# Bank.net
KiCad netlist of a schematic drawn in Altium Designer
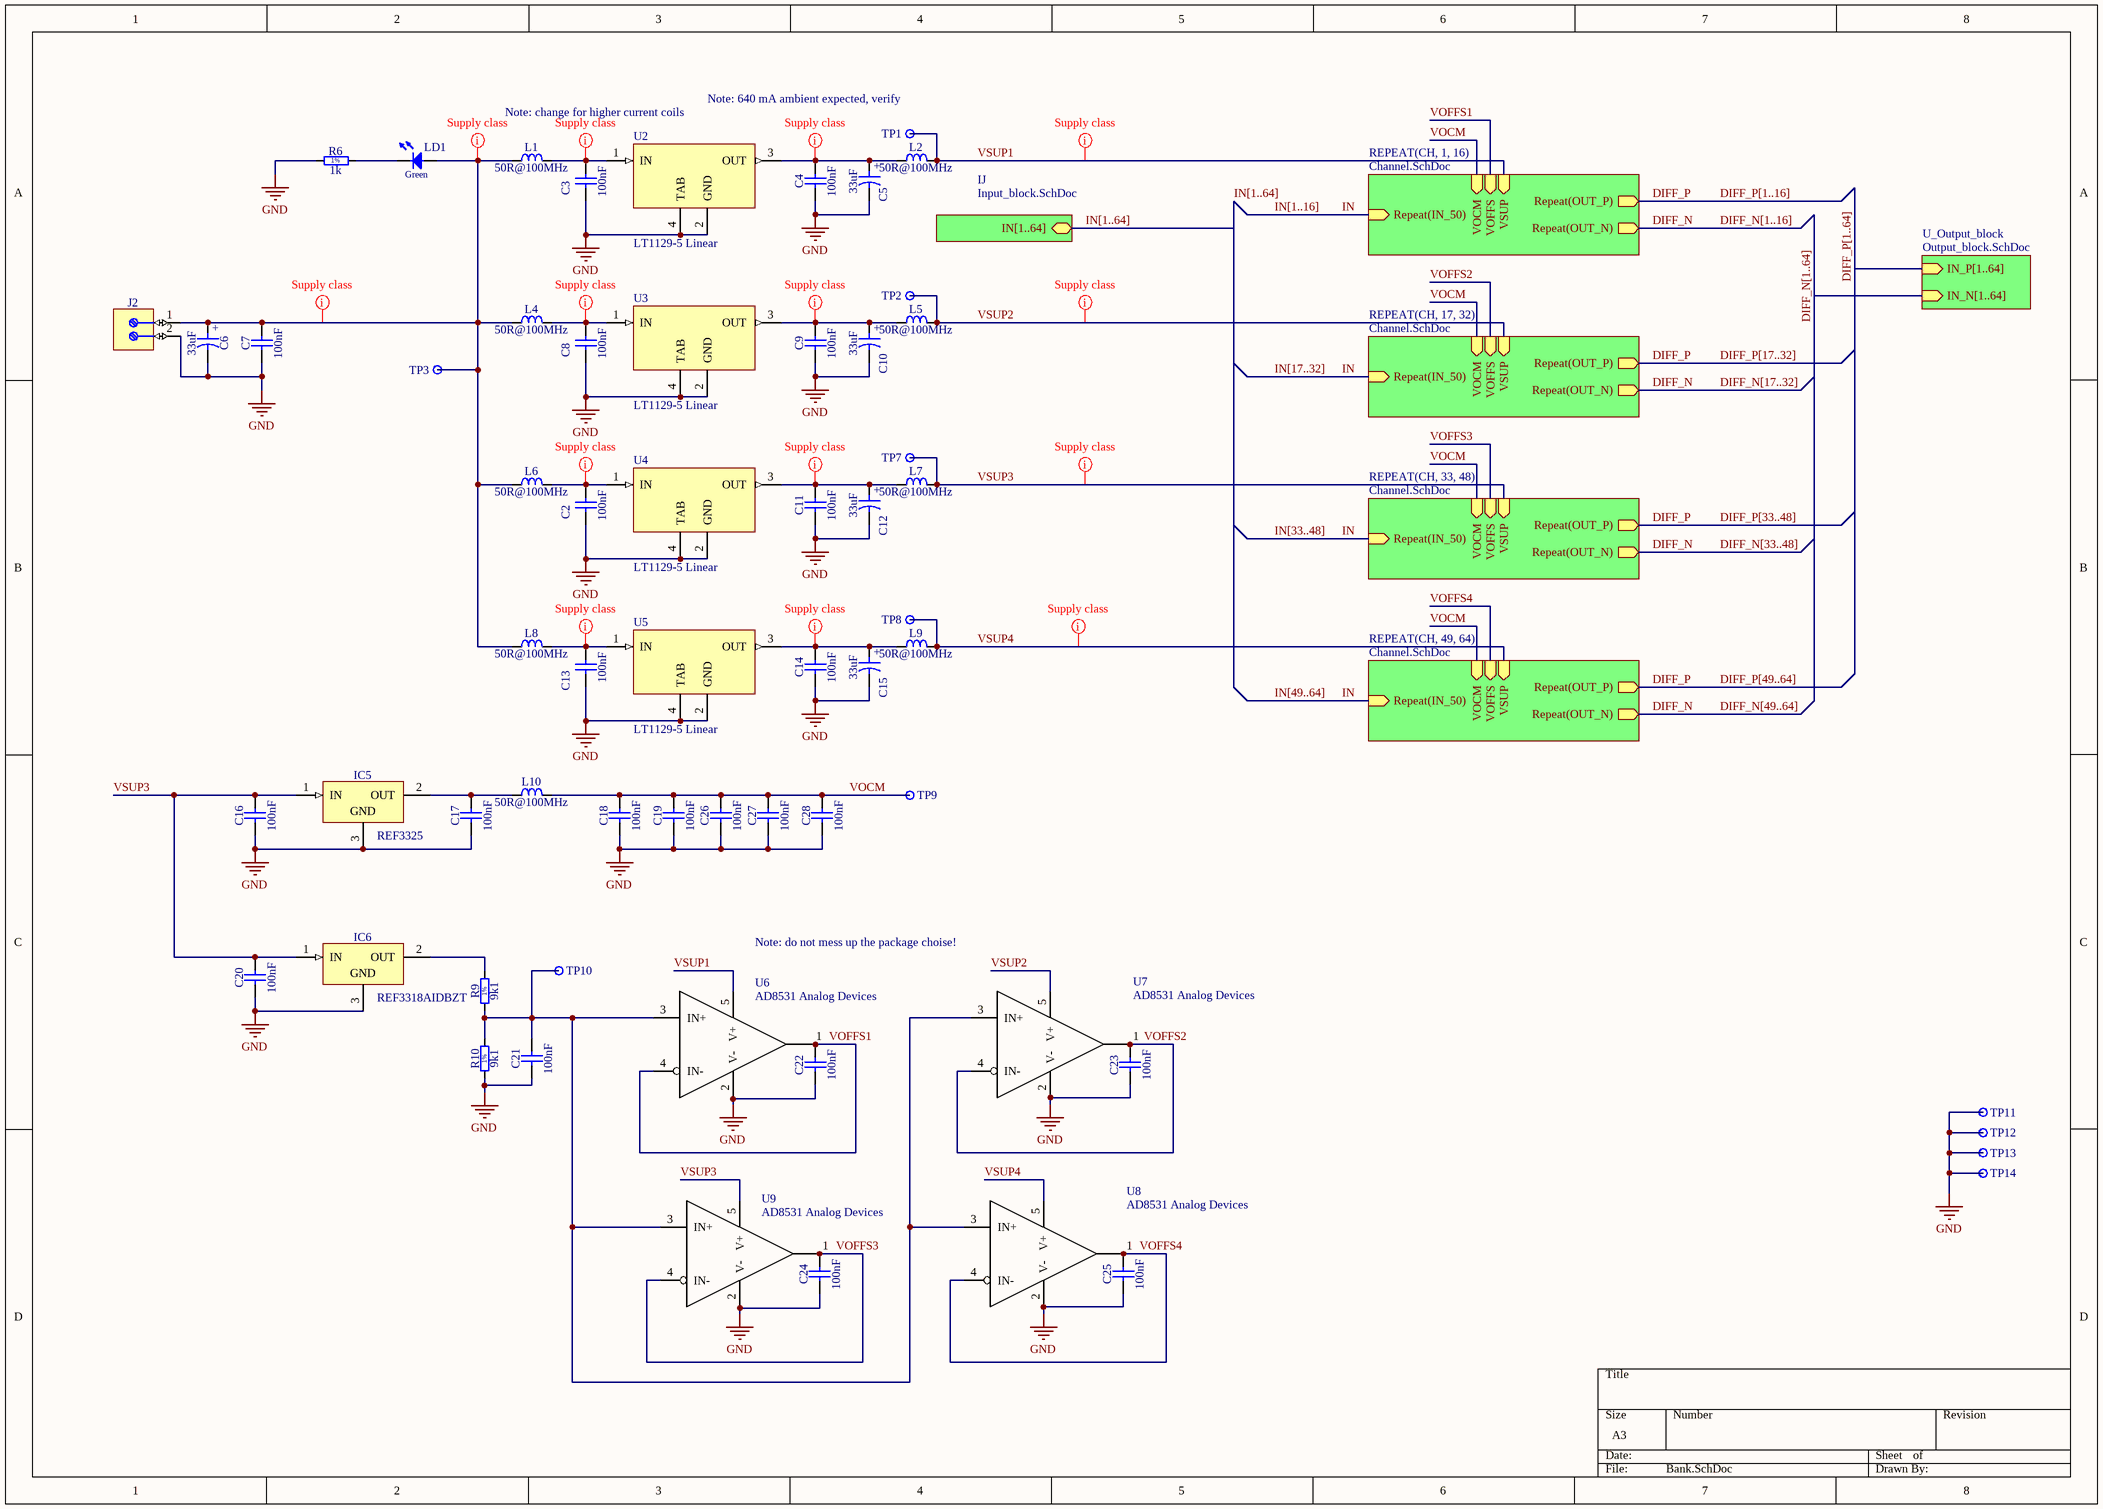
[diagram p0: Bank.SchDoc]

(export (version "E")
  (design (tool "Eeschema 10.0.6"))
  (components
    (comp (ref "C2")
      (value "100nF")
      (footprint "CAPC2012X135N")
      (description "Non-polarised capacitor")
      (fields
        (field (name "PART NUMBER") "CC0805_100NF_50V_10%_X7R")
        (field (name "VOLTAGE") "50V")
        (field (name "AUTHOR") "CERN DEM JLC")
      )
      (libsource (lib "Capacitors") (part "Capacitor - non polarized"))
    )
    (comp (ref "C3")
      (value "100nF")
      (footprint "CAPC2012X135N")
      (description "Non-polarised capacitor")
      (fields
        (field (name "PART NUMBER") "CC0805_100NF_50V_10%_X7R")
        (field (name "VOLTAGE") "50V")
        (field (name "AUTHOR") "CERN DEM JLC")
      )
      (libsource (lib "Capacitors") (part "Capacitor - non polarized"))
    )
    (comp (ref "C4")
      (value "100nF")
      (footprint "CAPC2012X135N")
      (description "Non-polarised capacitor")
      (fields
        (field (name "PART NUMBER") "CC0805_100NF_50V_10%_X7R")
        (field (name "VOLTAGE") "50V")
        (field (name "AUTHOR") "CERN DEM JLC")
      )
      (libsource (lib "Capacitors") (part "Capacitor - non polarized"))
    )
    (comp (ref "C5")
      (value "33uF")
      (footprint "CAPAE660X540N")
      (description "Polarised capacitor")
      (fields
        (field (name "PART NUMBER") "CAE660-540_33UF_25V_20%")
        (field (name "VOLTAGE") "25V")
        (field (name "AUTHOR") "CERN DEM JLC")
      )
      (libsource (lib "Capacitors") (part "Capacitor - polarized"))
    )
    (comp (ref "C6")
      (value "33uF")
      (footprint "CAPAE660X540N")
      (description "Polarised capacitor")
      (fields
        (field (name "PART NUMBER") "CAE660-540_33UF_25V_20%")
        (field (name "VOLTAGE") "25V")
        (field (name "AUTHOR") "CERN DEM JLC")
      )
      (libsource (lib "Capacitors") (part "Capacitor - polarized"))
    )
    (comp (ref "C7")
      (value "100nF")
      (footprint "CAPC2012X135N")
      (description "Non-polarised capacitor")
      (fields
        (field (name "PART NUMBER") "CC0805_100NF_50V_10%_X7R")
        (field (name "VOLTAGE") "50V")
        (field (name "AUTHOR") "CERN DEM JLC")
      )
      (libsource (lib "Capacitors") (part "Capacitor - non polarized"))
    )
    (comp (ref "C8")
      (value "100nF")
      (footprint "CAPC2012X135N")
      (description "Non-polarised capacitor")
      (fields
        (field (name "PART NUMBER") "CC0805_100NF_50V_10%_X7R")
        (field (name "VOLTAGE") "50V")
        (field (name "AUTHOR") "CERN DEM JLC")
      )
      (libsource (lib "Capacitors") (part "Capacitor - non polarized"))
    )
    (comp (ref "C9")
      (value "100nF")
      (footprint "CAPC2012X135N")
      (description "Non-polarised capacitor")
      (fields
        (field (name "PART NUMBER") "CC0805_100NF_50V_10%_X7R")
        (field (name "VOLTAGE") "50V")
        (field (name "AUTHOR") "CERN DEM JLC")
      )
      (libsource (lib "Capacitors") (part "Capacitor - non polarized"))
    )
    (comp (ref "C10")
      (value "33uF")
      (footprint "CAPAE660X540N")
      (description "Polarised capacitor")
      (fields
        (field (name "PART NUMBER") "CAE660-540_33UF_25V_20%")
        (field (name "VOLTAGE") "25V")
        (field (name "AUTHOR") "CERN DEM JLC")
      )
      (libsource (lib "Capacitors") (part "Capacitor - polarized"))
    )
    (comp (ref "C11")
      (value "100nF")
      (footprint "CAPC2012X135N")
      (description "Non-polarised capacitor")
      (fields
        (field (name "PART NUMBER") "CC0805_100NF_50V_10%_X7R")
        (field (name "VOLTAGE") "50V")
        (field (name "AUTHOR") "CERN DEM JLC")
      )
      (libsource (lib "Capacitors") (part "Capacitor - non polarized"))
    )
    (comp (ref "C12")
      (value "33uF")
      (footprint "CAPAE660X540N")
      (description "Polarised capacitor")
      (fields
        (field (name "PART NUMBER") "CAE660-540_33UF_25V_20%")
        (field (name "VOLTAGE") "25V")
        (field (name "AUTHOR") "CERN DEM JLC")
      )
      (libsource (lib "Capacitors") (part "Capacitor - polarized"))
    )
    (comp (ref "C13")
      (value "100nF")
      (footprint "CAPC2012X135N")
      (description "Non-polarised capacitor")
      (fields
        (field (name "PART NUMBER") "CC0805_100NF_50V_10%_X7R")
        (field (name "VOLTAGE") "50V")
        (field (name "AUTHOR") "CERN DEM JLC")
      )
      (libsource (lib "Capacitors") (part "Capacitor - non polarized"))
    )
    (comp (ref "C14")
      (value "100nF")
      (footprint "CAPC2012X135N")
      (description "Non-polarised capacitor")
      (fields
        (field (name "PART NUMBER") "CC0805_100NF_50V_10%_X7R")
        (field (name "VOLTAGE") "50V")
        (field (name "AUTHOR") "CERN DEM JLC")
      )
      (libsource (lib "Capacitors") (part "Capacitor - non polarized"))
    )
    (comp (ref "C15")
      (value "33uF")
      (footprint "CAPAE660X540N")
      (description "Polarised capacitor")
      (fields
        (field (name "PART NUMBER") "CAE660-540_33UF_25V_20%")
        (field (name "VOLTAGE") "25V")
        (field (name "AUTHOR") "CERN DEM JLC")
      )
      (libsource (lib "Capacitors") (part "Capacitor - polarized"))
    )
    (comp (ref "C16")
      (value "100nF")
      (footprint "CAPC2012X135N")
      (description "Non-polarised capacitor")
      (fields
        (field (name "PART NUMBER") "CC0805_100NF_50V_10%_X7R")
        (field (name "VOLTAGE") "50V")
        (field (name "AUTHOR") "CERN DEM JLC")
      )
      (libsource (lib "Capacitors") (part "Capacitor - non polarized"))
    )
    (comp (ref "C17")
      (value "100nF")
      (footprint "CAPC2012X135N")
      (description "Non-polarised capacitor")
      (fields
        (field (name "PART NUMBER") "CC0805_100NF_50V_10%_X7R")
        (field (name "VOLTAGE") "50V")
        (field (name "AUTHOR") "CERN DEM JLC")
      )
      (libsource (lib "Capacitors") (part "Capacitor - non polarized"))
    )
    (comp (ref "C18")
      (value "100nF")
      (footprint "CAPC2012X135N")
      (description "Non-polarised capacitor")
      (fields
        (field (name "PART NUMBER") "CC0805_100NF_50V_10%_X7R")
        (field (name "VOLTAGE") "50V")
        (field (name "AUTHOR") "CERN DEM JLC")
      )
      (libsource (lib "Capacitors") (part "Capacitor - non polarized"))
    )
    (comp (ref "C19")
      (value "100nF")
      (footprint "CAPC2012X135N")
      (description "Non-polarised capacitor")
      (fields
        (field (name "PART NUMBER") "CC0805_100NF_50V_10%_X7R")
        (field (name "VOLTAGE") "50V")
        (field (name "AUTHOR") "CERN DEM JLC")
      )
      (libsource (lib "Capacitors") (part "Capacitor - non polarized"))
    )
    (comp (ref "C20")
      (value "100nF")
      (footprint "CAPC2012X135N")
      (description "Non-polarised capacitor")
      (fields
        (field (name "PART NUMBER") "CC0805_100NF_50V_10%_X7R")
        (field (name "VOLTAGE") "50V")
        (field (name "AUTHOR") "CERN DEM JLC")
      )
      (libsource (lib "Capacitors") (part "Capacitor - non polarized"))
    )
    (comp (ref "C21")
      (value "100nF")
      (footprint "CAPC2012X135N")
      (description "Non-polarised capacitor")
      (fields
        (field (name "PART NUMBER") "CC0805_100NF_50V_10%_X7R")
        (field (name "VOLTAGE") "50V")
        (field (name "AUTHOR") "CERN DEM JLC")
      )
      (libsource (lib "Capacitors") (part "Capacitor - non polarized"))
    )
    (comp (ref "C22")
      (value "100nF")
      (footprint "CAPC2012X135N")
      (description "Non-polarised capacitor")
      (fields
        (field (name "PART NUMBER") "CC0805_100NF_50V_10%_X7R")
        (field (name "VOLTAGE") "50V")
        (field (name "AUTHOR") "CERN DEM JLC")
      )
      (libsource (lib "Capacitors") (part "Capacitor - non polarized"))
    )
    (comp (ref "C23")
      (value "100nF")
      (footprint "CAPC2012X135N")
      (description "Non-polarised capacitor")
      (fields
        (field (name "PART NUMBER") "CC0805_100NF_50V_10%_X7R")
        (field (name "VOLTAGE") "50V")
        (field (name "AUTHOR") "CERN DEM JLC")
      )
      (libsource (lib "Capacitors") (part "Capacitor - non polarized"))
    )
    (comp (ref "C24")
      (value "100nF")
      (footprint "CAPC2012X135N")
      (description "Non-polarised capacitor")
      (fields
        (field (name "PART NUMBER") "CC0805_100NF_50V_10%_X7R")
        (field (name "VOLTAGE") "50V")
        (field (name "AUTHOR") "CERN DEM JLC")
      )
      (libsource (lib "Capacitors") (part "Capacitor - non polarized"))
    )
    (comp (ref "C25")
      (value "100nF")
      (footprint "CAPC2012X135N")
      (description "Non-polarised capacitor")
      (fields
        (field (name "PART NUMBER") "CC0805_100NF_50V_10%_X7R")
        (field (name "VOLTAGE") "50V")
        (field (name "AUTHOR") "CERN DEM JLC")
      )
      (libsource (lib "Capacitors") (part "Capacitor - non polarized"))
    )
    (comp (ref "C26")
      (value "100nF")
      (footprint "CAPC2012X135N")
      (description "Non-polarised capacitor")
      (fields
        (field (name "PART NUMBER") "CC0805_100NF_50V_10%_X7R")
        (field (name "VOLTAGE") "50V")
        (field (name "AUTHOR") "CERN DEM JLC")
      )
      (libsource (lib "Capacitors") (part "Capacitor - non polarized"))
    )
    (comp (ref "C27")
      (value "100nF")
      (footprint "CAPC2012X135N")
      (description "Non-polarised capacitor")
      (fields
        (field (name "PART NUMBER") "CC0805_100NF_50V_10%_X7R")
        (field (name "VOLTAGE") "50V")
        (field (name "AUTHOR") "CERN DEM JLC")
      )
      (libsource (lib "Capacitors") (part "Capacitor - non polarized"))
    )
    (comp (ref "C28")
      (value "100nF")
      (footprint "CAPC2012X135N")
      (description "Non-polarised capacitor")
      (fields
        (field (name "PART NUMBER") "CC0805_100NF_50V_10%_X7R")
        (field (name "VOLTAGE") "50V")
        (field (name "AUTHOR") "CERN DEM JLC")
      )
      (libsource (lib "Capacitors") (part "Capacitor - non polarized"))
    )
    (comp (ref "IC5")
      (value "REF3325")
      (footprint "SOT95P237X112-3N")
      (description "3-Terminal Regulator 1=IN 2=OUT 3=GND")
      (fields (field (name "MANUFACTURER") "TEXAS INSTRUMENTS") (field (name "AUTHOR") "CERN DEM JLC"))
      (libsource (lib "ICs And Semiconductors") (part "REG3 1IN-2OUT-3GND"))
    )
    (comp (ref "IC6")
      (value "REF3318AIDBZT")
      (footprint "SOT95P237X112-3N")
      (description "3-Terminal Regulator 1=IN 2=OUT 3=GND")
      (fields (field (name "MANUFACTURER") "TEXAS INSTRUMENTS") (field (name "AUTHOR") "CERN DEM JLC"))
      (libsource (lib "ICs And Semiconductors") (part "REG3 1IN-2OUT-3GND"))
    )
    (comp (ref "J2")
      (value "Terminal")
      (footprint "WIELAND_25.161.0253.0")
      (description "Terminal Block, 2 Positions, Screw Connection")
      (fields
        (field (name "PART NUMBER") "WIELAND_25.161.0253.0")
        (field (name "MANUFACTURER") "WIELAND")
        (field (name "AUTHOR") "CERN DEM JLC")
      )
      (libsource (lib "Connectors") (part "Terminal Block_2 Positions_Screw Connection"))
    )
    (comp (ref "L1")
      (value "50R@100MHz")
      (footprint "IND_MURATA_BLM31PG")
      (description "Inductor")
      (fields
        (field (name "PART NUMBER") "IND1206_MURATA_BLM31PG500SN1")
        (field (name "POWER") "3.5A")
        (field (name "AUTHOR") "CERN DEM JLC")
      )
      (libsource (lib "Inductors & Transformers") (part "Inductor"))
    )
    (comp (ref "L2")
      (value "50R@100MHz")
      (footprint "IND_MURATA_BLM31PG")
      (description "Inductor")
      (fields
        (field (name "PART NUMBER") "IND1206_MURATA_BLM31PG500SN1")
        (field (name "POWER") "3.5A")
        (field (name "AUTHOR") "CERN DEM JLC")
      )
      (libsource (lib "Inductors & Transformers") (part "Inductor"))
    )
    (comp (ref "L4")
      (value "50R@100MHz")
      (footprint "IND_MURATA_BLM31PG")
      (description "Inductor")
      (fields
        (field (name "PART NUMBER") "IND1206_MURATA_BLM31PG500SN1")
        (field (name "POWER") "3.5A")
        (field (name "AUTHOR") "CERN DEM JLC")
      )
      (libsource (lib "Inductors & Transformers") (part "Inductor"))
    )
    (comp (ref "L5")
      (value "50R@100MHz")
      (footprint "IND_MURATA_BLM31PG")
      (description "Inductor")
      (fields
        (field (name "PART NUMBER") "IND1206_MURATA_BLM31PG500SN1")
        (field (name "POWER") "3.5A")
        (field (name "AUTHOR") "CERN DEM JLC")
      )
      (libsource (lib "Inductors & Transformers") (part "Inductor"))
    )
    (comp (ref "L6")
      (value "50R@100MHz")
      (footprint "IND_MURATA_BLM31PG")
      (description "Inductor")
      (fields
        (field (name "PART NUMBER") "IND1206_MURATA_BLM31PG500SN1")
        (field (name "POWER") "3.5A")
        (field (name "AUTHOR") "CERN DEM JLC")
      )
      (libsource (lib "Inductors & Transformers") (part "Inductor"))
    )
    (comp (ref "L7")
      (value "50R@100MHz")
      (footprint "IND_MURATA_BLM31PG")
      (description "Inductor")
      (fields
        (field (name "PART NUMBER") "IND1206_MURATA_BLM31PG500SN1")
        (field (name "POWER") "3.5A")
        (field (name "AUTHOR") "CERN DEM JLC")
      )
      (libsource (lib "Inductors & Transformers") (part "Inductor"))
    )
    (comp (ref "L8")
      (value "50R@100MHz")
      (footprint "IND_MURATA_BLM31PG")
      (description "Inductor")
      (fields
        (field (name "PART NUMBER") "IND1206_MURATA_BLM31PG500SN1")
        (field (name "POWER") "3.5A")
        (field (name "AUTHOR") "CERN DEM JLC")
      )
      (libsource (lib "Inductors & Transformers") (part "Inductor"))
    )
    (comp (ref "L9")
      (value "50R@100MHz")
      (footprint "IND_MURATA_BLM31PG")
      (description "Inductor")
      (fields
        (field (name "PART NUMBER") "IND1206_MURATA_BLM31PG500SN1")
        (field (name "POWER") "3.5A")
        (field (name "AUTHOR") "CERN DEM JLC")
      )
      (libsource (lib "Inductors & Transformers") (part "Inductor"))
    )
    (comp (ref "L10")
      (value "50R@100MHz")
      (footprint "IND_MURATA_BLM31PG")
      (description "Inductor")
      (fields
        (field (name "PART NUMBER") "IND1206_MURATA_BLM31PG500SN1")
        (field (name "POWER") "3.5A")
        (field (name "AUTHOR") "CERN DEM JLC")
      )
      (libsource (lib "Inductors & Transformers") (part "Inductor"))
    )
    (comp (ref "LD1")
      (value "Green")
      (footprint "LED_OSRAM_LGR971")
      (description "LED Green 1C 2A")
      (fields
        (field (name "PART NUMBER") "LED_OSRAM_LGR971")
        (field (name "MANUFACTURER") "OSRAM")
        (field (name "AUTHOR") "CERN DEM JLC")
      )
      (libsource (lib "ICs And Semiconductors") (part "LED Green 1C 2A"))
    )
    (comp (ref "R6")
      (value "1k")
      (footprint "RESC2012X60N")
      (description "Resistor - 1%")
      (fields
        (field (name "PART NUMBER") "R0805_1K_1%_0.125W_100PPM")
        (field (name "POWER") "0.125W")
        (field (name "AUTHOR") "CERN DEM JLC")
      )
      (libsource (lib "Resistors") (part "Resistor - 1%"))
    )
    (comp (ref "R9")
      (value "9k1")
      (footprint "RESC2012X60N")
      (description "Resistor - 1%")
      (fields
        (field (name "PART NUMBER") "R0805_9K1_1%_0.125W_100PPM")
        (field (name "POWER") "0.125W")
        (field (name "AUTHOR") "CERN DEM JLC")
      )
      (libsource (lib "Resistors") (part "Resistor - 1%"))
    )
    (comp (ref "R10")
      (value "9k1")
      (footprint "RESC2012X60N")
      (description "Resistor - 1%")
      (fields
        (field (name "PART NUMBER") "R0805_9K1_1%_0.125W_100PPM")
        (field (name "POWER") "0.125W")
        (field (name "AUTHOR") "CERN DEM JLC")
      )
      (libsource (lib "Resistors") (part "Resistor - 1%"))
    )
    (comp (ref "TP1")
      (value "Test Point")
      (footprint "VERO_20-313145")
      (fields
        (field (name "PART NUMBER") "VERO_20-313145")
        (field (name "MANUFACTURER") "VERO TECHNOLOGIES")
        (field (name "MANUFACTURER PART NUMBER") "20-313145")
        (field (name "AUTHOR") "CERN DEM JLC")
      )
      (libsource (lib "Connectors") (part "Test Point"))
    )
    (comp (ref "TP2")
      (value "Test Point")
      (footprint "VERO_20-313145")
      (fields
        (field (name "PART NUMBER") "VERO_20-313145")
        (field (name "MANUFACTURER") "VERO TECHNOLOGIES")
        (field (name "MANUFACTURER PART NUMBER") "20-313145")
        (field (name "AUTHOR") "CERN DEM JLC")
      )
      (libsource (lib "Connectors") (part "Test Point"))
    )
    (comp (ref "TP3")
      (value "Test Point")
      (footprint "VERO_20-313145")
      (fields
        (field (name "PART NUMBER") "VERO_20-313145")
        (field (name "MANUFACTURER") "VERO TECHNOLOGIES")
        (field (name "MANUFACTURER PART NUMBER") "20-313145")
        (field (name "AUTHOR") "CERN DEM JLC")
      )
      (libsource (lib "Connectors") (part "Test Point"))
    )
    (comp (ref "TP7")
      (value "Test Point")
      (footprint "VERO_20-313145")
      (fields
        (field (name "PART NUMBER") "VERO_20-313145")
        (field (name "MANUFACTURER") "VERO TECHNOLOGIES")
        (field (name "MANUFACTURER PART NUMBER") "20-313145")
        (field (name "AUTHOR") "CERN DEM JLC")
      )
      (libsource (lib "Connectors") (part "Test Point"))
    )
    (comp (ref "TP8")
      (value "Test Point")
      (footprint "VERO_20-313145")
      (fields
        (field (name "PART NUMBER") "VERO_20-313145")
        (field (name "MANUFACTURER") "VERO TECHNOLOGIES")
        (field (name "MANUFACTURER PART NUMBER") "20-313145")
        (field (name "AUTHOR") "CERN DEM JLC")
      )
      (libsource (lib "Connectors") (part "Test Point"))
    )
    (comp (ref "TP9")
      (value "Test Point")
      (footprint "VERO_20-313145")
      (fields
        (field (name "PART NUMBER") "VERO_20-313145")
        (field (name "MANUFACTURER") "VERO TECHNOLOGIES")
        (field (name "MANUFACTURER PART NUMBER") "20-313145")
        (field (name "AUTHOR") "CERN DEM JLC")
      )
      (libsource (lib "Connectors") (part "Test Point"))
    )
    (comp (ref "TP10")
      (value "Test Point")
      (footprint "VERO_20-313145")
      (fields
        (field (name "PART NUMBER") "VERO_20-313145")
        (field (name "MANUFACTURER") "VERO TECHNOLOGIES")
        (field (name "MANUFACTURER PART NUMBER") "20-313145")
        (field (name "AUTHOR") "CERN DEM JLC")
      )
      (libsource (lib "Connectors") (part "Test Point"))
    )
    (comp (ref "TP11")
      (value "Test Point")
      (footprint "VERO_20-313145")
      (fields
        (field (name "PART NUMBER") "VERO_20-313145")
        (field (name "MANUFACTURER") "VERO TECHNOLOGIES")
        (field (name "MANUFACTURER PART NUMBER") "20-313145")
        (field (name "AUTHOR") "CERN DEM JLC")
      )
      (libsource (lib "Connectors") (part "Test Point"))
    )
    (comp (ref "TP12")
      (value "Test Point")
      (footprint "VERO_20-313145")
      (fields
        (field (name "PART NUMBER") "VERO_20-313145")
        (field (name "MANUFACTURER") "VERO TECHNOLOGIES")
        (field (name "MANUFACTURER PART NUMBER") "20-313145")
        (field (name "AUTHOR") "CERN DEM JLC")
      )
      (libsource (lib "Connectors") (part "Test Point"))
    )
    (comp (ref "TP13")
      (value "Test Point")
      (footprint "VERO_20-313145")
      (fields
        (field (name "PART NUMBER") "VERO_20-313145")
        (field (name "MANUFACTURER") "VERO TECHNOLOGIES")
        (field (name "MANUFACTURER PART NUMBER") "20-313145")
        (field (name "AUTHOR") "CERN DEM JLC")
      )
      (libsource (lib "Connectors") (part "Test Point"))
    )
    (comp (ref "TP14")
      (value "Test Point")
      (footprint "VERO_20-313145")
      (fields
        (field (name "PART NUMBER") "VERO_20-313145")
        (field (name "MANUFACTURER") "VERO TECHNOLOGIES")
        (field (name "MANUFACTURER PART NUMBER") "20-313145")
        (field (name "AUTHOR") "CERN DEM JLC")
      )
      (libsource (lib "Connectors") (part "Test Point"))
    )
    (comp (ref "U2")
      (value "LT1129-5 Linear")
      (footprint "SOT230P700X175-4N")
      (fields (field (name "MANUFACTURER") "Linear"))
      (libsource (lib "Additional") (part "LT1129-5"))
    )
    (comp (ref "U3")
      (value "LT1129-5 Linear")
      (footprint "SOT230P700X175-4N")
      (fields (field (name "MANUFACTURER") "Linear"))
      (libsource (lib "Additional") (part "LT1129-5"))
    )
    (comp (ref "U4")
      (value "LT1129-5 Linear")
      (footprint "SOT230P700X175-4N")
      (fields (field (name "MANUFACTURER") "Linear"))
      (libsource (lib "Additional") (part "LT1129-5"))
    )
    (comp (ref "U5")
      (value "LT1129-5 Linear")
      (footprint "SOT230P700X175-4N")
      (fields (field (name "MANUFACTURER") "Linear"))
      (libsource (lib "Additional") (part "LT1129-5"))
    )
    (comp (ref "U6")
      (value "AD8531 Analog Devices")
      (footprint "SOT95P285X145-5N")
      (fields (field (name "MANUFACTURER") "Analog Devices"))
      (libsource (lib "Additional") (part "AD8531"))
    )
    (comp (ref "U7")
      (value "AD8531 Analog Devices")
      (footprint "SOT95P285X145-5N")
      (fields (field (name "MANUFACTURER") "Analog Devices"))
      (libsource (lib "Additional") (part "AD8531"))
    )
    (comp (ref "U8")
      (value "AD8531 Analog Devices")
      (footprint "SOT95P285X145-5N")
      (fields (field (name "MANUFACTURER") "Analog Devices"))
      (libsource (lib "Additional") (part "AD8531"))
    )
    (comp (ref "U9")
      (value "AD8531 Analog Devices")
      (footprint "SOT95P285X145-5N")
      (fields (field (name "MANUFACTURER") "Analog Devices"))
      (libsource (lib "Additional") (part "AD8531"))
    )
  )
  (nets
    (net (code "211") (name "/VOCM") (class "Default")
      (node (ref "C18") (pin "2") (pinfunction "2_2") (pintype "passive"))
      (node (ref "C19") (pin "2") (pinfunction "2_2") (pintype "passive"))
      (node (ref "C26") (pin "2") (pinfunction "2_2") (pintype "passive"))
      (node (ref "C27") (pin "2") (pinfunction "2_2") (pintype "passive"))
      (node (ref "C28") (pin "2") (pinfunction "2_2") (pintype "passive"))
      (node (ref "L10") (pin "2") (pinfunction "2_2") (pintype "passive"))
      (node (ref "TP9") (pin "1") (pinfunction "1_1") (pintype "bidirectional"))
    )
    (net (code "212") (name "/VOFFS1") (class "Default")
      (node (ref "C22") (pin "2") (pinfunction "2_2") (pintype "passive"))
      (node (ref "U6") (pin "1") (pinfunction "OUT+_1") (pintype "passive"))
      (node (ref "U6") (pin "4") (pinfunction "IN-_4") (pintype "passive"))
    )
    (net (code "213") (name "/VOFFS2") (class "Default")
      (node (ref "C23") (pin "2") (pinfunction "2_2") (pintype "passive"))
      (node (ref "U7") (pin "1") (pinfunction "OUT+_1") (pintype "passive"))
      (node (ref "U7") (pin "4") (pinfunction "IN-_4") (pintype "passive"))
    )
    (net (code "214") (name "/VOFFS3") (class "Default")
      (node (ref "C24") (pin "2") (pinfunction "2_2") (pintype "passive"))
      (node (ref "U9") (pin "1") (pinfunction "OUT+_1") (pintype "passive"))
      (node (ref "U9") (pin "4") (pinfunction "IN-_4") (pintype "passive"))
    )
    (net (code "215") (name "/VOFFS4") (class "Default")
      (node (ref "C25") (pin "2") (pinfunction "2_2") (pintype "passive"))
      (node (ref "U8") (pin "1") (pinfunction "OUT+_1") (pintype "passive"))
      (node (ref "U8") (pin "4") (pinfunction "IN-_4") (pintype "passive"))
    )
    (net (code "216") (name "/VSUP1") (class "Default")
      (node (ref "L2") (pin "2") (pinfunction "2_2") (pintype "passive"))
      (node (ref "TP1") (pin "1") (pinfunction "1_1") (pintype "bidirectional"))
      (node (ref "U6") (pin "5") (pinfunction "V+_5") (pintype "passive"))
    )
    (net (code "217") (name "/VSUP2") (class "Default")
      (node (ref "L5") (pin "2") (pinfunction "2_2") (pintype "passive"))
      (node (ref "TP2") (pin "1") (pinfunction "1_1") (pintype "bidirectional"))
      (node (ref "U7") (pin "5") (pinfunction "V+_5") (pintype "passive"))
    )
    (net (code "218") (name "/VSUP3") (class "Default")
      (node (ref "C16") (pin "2") (pinfunction "2_2") (pintype "passive"))
      (node (ref "C20") (pin "2") (pinfunction "2_2") (pintype "passive"))
      (node (ref "IC5") (pin "1") (pinfunction "IN_1") (pintype "input"))
      (node (ref "IC6") (pin "1") (pinfunction "IN_1") (pintype "input"))
      (node (ref "L7") (pin "2") (pinfunction "2_2") (pintype "passive"))
      (node (ref "TP7") (pin "1") (pinfunction "1_1") (pintype "bidirectional"))
      (node (ref "U9") (pin "5") (pinfunction "V+_5") (pintype "passive"))
    )
    (net (code "219") (name "/VSUP4") (class "Default")
      (node (ref "L9") (pin "2") (pinfunction "2_2") (pintype "passive"))
      (node (ref "TP8") (pin "1") (pinfunction "1_1") (pintype "bidirectional"))
      (node (ref "U8") (pin "5") (pinfunction "V+_5") (pintype "passive"))
    )
    (net (code "220") (name "GND") (class "Default")
      (node (ref "C10") (pin "2") (pinfunction "2_2") (pintype "passive"))
      (node (ref "C11") (pin "1") (pinfunction "1_1") (pintype "passive"))
      (node (ref "C12") (pin "2") (pinfunction "2_2") (pintype "passive"))
      (node (ref "C13") (pin "1") (pinfunction "1_1") (pintype "passive"))
      (node (ref "C14") (pin "1") (pinfunction "1_1") (pintype "passive"))
      (node (ref "C15") (pin "2") (pinfunction "2_2") (pintype "passive"))
      (node (ref "C16") (pin "1") (pinfunction "1_1") (pintype "passive"))
      (node (ref "C17") (pin "1") (pinfunction "1_1") (pintype "passive"))
      (node (ref "C18") (pin "1") (pinfunction "1_1") (pintype "passive"))
      (node (ref "C19") (pin "1") (pinfunction "1_1") (pintype "passive"))
      (node (ref "C2") (pin "1") (pinfunction "1_1") (pintype "passive"))
      (node (ref "C20") (pin "1") (pinfunction "1_1") (pintype "passive"))
      (node (ref "C21") (pin "1") (pinfunction "1_1") (pintype "passive"))
      (node (ref "C22") (pin "1") (pinfunction "1_1") (pintype "passive"))
      (node (ref "C23") (pin "1") (pinfunction "1_1") (pintype "passive"))
      (node (ref "C24") (pin "1") (pinfunction "1_1") (pintype "passive"))
      (node (ref "C25") (pin "1") (pinfunction "1_1") (pintype "passive"))
      (node (ref "C26") (pin "1") (pinfunction "1_1") (pintype "passive"))
      (node (ref "C27") (pin "1") (pinfunction "1_1") (pintype "passive"))
      (node (ref "C28") (pin "1") (pinfunction "1_1") (pintype "passive"))
      (node (ref "C3") (pin "1") (pinfunction "1_1") (pintype "passive"))
      (node (ref "C4") (pin "1") (pinfunction "1_1") (pintype "passive"))
      (node (ref "C5") (pin "2") (pinfunction "2_2") (pintype "passive"))
      (node (ref "C6") (pin "2") (pinfunction "2_2") (pintype "passive"))
      (node (ref "C7") (pin "1") (pinfunction "1_1") (pintype "passive"))
      (node (ref "C8") (pin "1") (pinfunction "1_1") (pintype "passive"))
      (node (ref "C9") (pin "1") (pinfunction "1_1") (pintype "passive"))
      (node (ref "IC5") (pin "3") (pinfunction "GND_3") (pintype "power_in"))
      (node (ref "IC6") (pin "3") (pinfunction "GND_3") (pintype "power_in"))
      (node (ref "J2") (pin "2") (pinfunction "2_2") (pintype "bidirectional"))
      (node (ref "R10") (pin "1") (pinfunction "1_1") (pintype "passive"))
      (node (ref "R6") (pin "1") (pinfunction "1_1") (pintype "passive"))
      (node (ref "TP11") (pin "1") (pinfunction "1_1") (pintype "bidirectional"))
      (node (ref "TP12") (pin "1") (pinfunction "1_1") (pintype "bidirectional"))
      (node (ref "TP13") (pin "1") (pinfunction "1_1") (pintype "bidirectional"))
      (node (ref "TP14") (pin "1") (pinfunction "1_1") (pintype "bidirectional"))
      (node (ref "U2") (pin "2") (pinfunction "GND_2") (pintype "power_in"))
      (node (ref "U2") (pin "4") (pinfunction "TAB_4") (pintype "power_in"))
      (node (ref "U3") (pin "2") (pinfunction "GND_2") (pintype "power_in"))
      (node (ref "U3") (pin "4") (pinfunction "TAB_4") (pintype "power_in"))
      (node (ref "U4") (pin "2") (pinfunction "GND_2") (pintype "power_in"))
      (node (ref "U4") (pin "4") (pinfunction "TAB_4") (pintype "power_in"))
      (node (ref "U5") (pin "2") (pinfunction "GND_2") (pintype "power_in"))
      (node (ref "U5") (pin "4") (pinfunction "TAB_4") (pintype "power_in"))
      (node (ref "U6") (pin "2") (pinfunction "V-_2") (pintype "passive"))
      (node (ref "U7") (pin "2") (pinfunction "V-_2") (pintype "passive"))
      (node (ref "U8") (pin "2") (pinfunction "V-_2") (pintype "passive"))
      (node (ref "U9") (pin "2") (pinfunction "V-_2") (pintype "passive"))
    )
    (net (code "221") (name "Net-(IC5-OUT)") (class "Default")
      (node (ref "C17") (pin "2") (pinfunction "2_2") (pintype "passive"))
      (node (ref "IC5") (pin "2") (pinfunction "OUT_2") (pintype "power_in"))
      (node (ref "L10") (pin "1") (pinfunction "1_1") (pintype "passive"))
    )
    (net (code "222") (name "Net-(IC6-OUT)") (class "Default")
      (node (ref "IC6") (pin "2") (pinfunction "OUT_2") (pintype "power_in"))
      (node (ref "R9") (pin "2") (pinfunction "2_2") (pintype "passive"))
    )
    (net (code "223") (name "Net-(LD1-A)") (class "Default")
      (node (ref "C6") (pin "1") (pinfunction "1_1") (pintype "passive"))
      (node (ref "C7") (pin "2") (pinfunction "2_2") (pintype "passive"))
      (node (ref "J2") (pin "1") (pinfunction "1_1") (pintype "bidirectional"))
      (node (ref "L1") (pin "1") (pinfunction "1_1") (pintype "passive"))
      (node (ref "L4") (pin "1") (pinfunction "1_1") (pintype "passive"))
      (node (ref "L6") (pin "1") (pinfunction "1_1") (pintype "passive"))
      (node (ref "L8") (pin "1") (pinfunction "1_1") (pintype "passive"))
      (node (ref "LD1") (pin "2") (pinfunction "A_2") (pintype "passive"))
      (node (ref "TP3") (pin "1") (pinfunction "1_1") (pintype "bidirectional"))
    )
    (net (code "224") (name "Net-(LD1-C)") (class "Default")
      (node (ref "LD1") (pin "1") (pinfunction "C_1") (pintype "passive"))
      (node (ref "R6") (pin "2") (pinfunction "2_2") (pintype "passive"))
    )
    (net (code "225") (name "Net-(U2-IN)") (class "Default")
      (node (ref "C3") (pin "2") (pinfunction "2_2") (pintype "passive"))
      (node (ref "L1") (pin "2") (pinfunction "2_2") (pintype "passive"))
      (node (ref "U2") (pin "1") (pinfunction "IN_1") (pintype "input"))
    )
    (net (code "226") (name "Net-(U2-OUT)") (class "Default")
      (node (ref "C4") (pin "2") (pinfunction "2_2") (pintype "passive"))
      (node (ref "C5") (pin "1") (pinfunction "1_1") (pintype "passive"))
      (node (ref "L2") (pin "1") (pinfunction "1_1") (pintype "passive"))
      (node (ref "U2") (pin "3") (pinfunction "OUT_3") (pintype "output"))
    )
    (net (code "227") (name "Net-(U3-IN)") (class "Default")
      (node (ref "C8") (pin "2") (pinfunction "2_2") (pintype "passive"))
      (node (ref "L4") (pin "2") (pinfunction "2_2") (pintype "passive"))
      (node (ref "U3") (pin "1") (pinfunction "IN_1") (pintype "input"))
    )
    (net (code "228") (name "Net-(U3-OUT)") (class "Default")
      (node (ref "C10") (pin "1") (pinfunction "1_1") (pintype "passive"))
      (node (ref "C9") (pin "2") (pinfunction "2_2") (pintype "passive"))
      (node (ref "L5") (pin "1") (pinfunction "1_1") (pintype "passive"))
      (node (ref "U3") (pin "3") (pinfunction "OUT_3") (pintype "output"))
    )
    (net (code "229") (name "Net-(U4-IN)") (class "Default")
      (node (ref "C2") (pin "2") (pinfunction "2_2") (pintype "passive"))
      (node (ref "L6") (pin "2") (pinfunction "2_2") (pintype "passive"))
      (node (ref "U4") (pin "1") (pinfunction "IN_1") (pintype "input"))
    )
    (net (code "230") (name "Net-(U4-OUT)") (class "Default")
      (node (ref "C11") (pin "2") (pinfunction "2_2") (pintype "passive"))
      (node (ref "C12") (pin "1") (pinfunction "1_1") (pintype "passive"))
      (node (ref "L7") (pin "1") (pinfunction "1_1") (pintype "passive"))
      (node (ref "U4") (pin "3") (pinfunction "OUT_3") (pintype "output"))
    )
    (net (code "231") (name "Net-(U5-IN)") (class "Default")
      (node (ref "C13") (pin "2") (pinfunction "2_2") (pintype "passive"))
      (node (ref "L8") (pin "2") (pinfunction "2_2") (pintype "passive"))
      (node (ref "U5") (pin "1") (pinfunction "IN_1") (pintype "input"))
    )
    (net (code "232") (name "Net-(U5-OUT)") (class "Default")
      (node (ref "C14") (pin "2") (pinfunction "2_2") (pintype "passive"))
      (node (ref "C15") (pin "1") (pinfunction "1_1") (pintype "passive"))
      (node (ref "L9") (pin "1") (pinfunction "1_1") (pintype "passive"))
      (node (ref "U5") (pin "3") (pinfunction "OUT_3") (pintype "output"))
    )
    (net (code "233") (name "Net-(U6-IN+)") (class "Default")
      (node (ref "C21") (pin "2") (pinfunction "2_2") (pintype "passive"))
      (node (ref "R10") (pin "2") (pinfunction "2_2") (pintype "passive"))
      (node (ref "R9") (pin "1") (pinfunction "1_1") (pintype "passive"))
      (node (ref "TP10") (pin "1") (pinfunction "1_1") (pintype "bidirectional"))
      (node (ref "U6") (pin "3") (pinfunction "IN+_3") (pintype "passive"))
      (node (ref "U7") (pin "3") (pinfunction "IN+_3") (pintype "passive"))
      (node (ref "U8") (pin "3") (pinfunction "IN+_3") (pintype "passive"))
      (node (ref "U9") (pin "3") (pinfunction "IN+_3") (pintype "passive"))
    )
  )
)
